# POWER_MC33063.net
KiCad netlist of a schematic drawn in Altium Designer
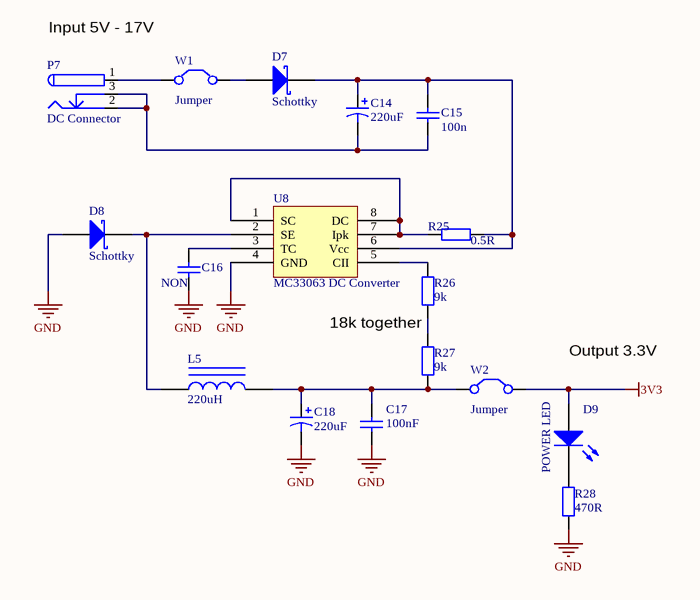
[diagram p0: POWER_MC33063.SchDoc]

(export (version "E")
  (design (tool "Eeschema 10.0.6"))
  (components
    (comp (ref "C14")
      (value "220uF")
      (footprint "SMD CAPACITOR 220uF")
      (description "Capacitor")
      (fields (field (name "PUBLISHER") "Altium Limited"))
      (libsource (lib "Miscellaneous Devices") (part "Cap Pol1"))
    )
    (comp (ref "C15")
      (value "100n")
      (footprint "1608[0603]")
      (description "Capacitor")
      (fields (field (name "PUBLISHER") "Altium Limited"))
      (libsource (lib "Miscellaneous Devices") (part "Cap"))
    )
    (comp (ref "C16")
      (value "NON")
      (footprint "1608[0603]")
      (description "Capacitor")
      (fields (field (name "PUBLISHER") "Altium Limited"))
      (libsource (lib "Miscellaneous Devices") (part "Cap"))
    )
    (comp (ref "C17")
      (value "100nF")
      (footprint "1608[0603]")
      (description "Capacitor")
      (fields (field (name "PUBLISHER") "Altium Limited"))
      (libsource (lib "Miscellaneous Devices") (part "Cap"))
    )
    (comp (ref "C18")
      (value "220uF")
      (footprint "SMD CAPACITOR 220uF")
      (description "Polarized Capacitor (Radial)")
      (fields (field (name "PUBLISHER") "Altium Limited"))
      (libsource (lib "Miscellaneous Devices") (part "Cap Pol1"))
    )
    (comp (ref "D7")
      (value "Schottky")
      (footprint "SMB")
      (description "Schottky Diode")
      (fields (field (name "PUBLISHER") "Altium Limited"))
      (libsource (lib "Miscellaneous Devices") (part "D Schottky"))
    )
    (comp (ref "D8")
      (value "Schottky")
      (footprint "SMB")
      (description "Schottky Diode")
      (fields (field (name "PUBLISHER") "Altium Limited"))
      (libsource (lib "Miscellaneous Devices") (part "D Schottky"))
    )
    (comp (ref "D9")
      (value "POWER LED")
      (footprint "LED-1")
      (description "Typical INFRARED GaAs LED")
      (fields (field (name "PUBLISHER") "Altium Limited"))
      (libsource (lib "Miscellaneous Devices") (part "LED0"))
    )
    (comp (ref "L5")
      (value "220uH")
      (footprint "Inductor")
      (description "Magnetic-Core Inductor")
      (fields (field (name "PUBLISHER") "Altium Limited"))
      (libsource (lib "Miscellaneous Devices") (part "Inductor Iron"))
    )
    (comp (ref "P7")
      (value "DC Connector")
      (footprint "DC Connector")
      (description "DC Power Connector")
      (libsource (lib "LukaLIBRARY") (part "DC Connector"))
    )
    (comp (ref "R25")
      (value "0.5R")
      (footprint "1608[0603]")
      (description "Resistor")
      (fields (field (name "PUBLISHER") "Altium Limited"))
      (libsource (lib "") (part "Res2_1"))
    )
    (comp (ref "R26")
      (value "9k")
      (footprint "1608[0603]")
      (description "Resistor")
      (fields (field (name "PUBLISHER") "Altium Limited"))
      (libsource (lib "Miscellaneous Devices") (part "Res2"))
    )
    (comp (ref "R27")
      (value "9k")
      (footprint "1608[0603]")
      (description "Resistor")
      (fields (field (name "PUBLISHER") "Altium Limited"))
      (libsource (lib "Miscellaneous Devices") (part "Res2"))
    )
    (comp (ref "R28")
      (value "470R")
      (footprint "1608[0603]")
      (description "Resistor")
      (fields (field (name "PUBLISHER") "Altium Limited"))
      (libsource (lib "Miscellaneous Devices") (part "Res2"))
    )
    (comp (ref "U8")
      (value "MC33063 DC Converter")
      (footprint "SO8_N")
      (libsource (lib "LukaLIBRARY") (part "MC33063 - MC34063 DC DC"))
    )
    (comp (ref "W1")
      (value "Jumper")
      (footprint "HDR1X2")
      (description "Jumper Wire")
      (fields (field (name "PUBLISHER") "Altium Limited"))
      (libsource (lib "Miscellaneous Devices") (part "Jumper"))
    )
    (comp (ref "W2")
      (value "Jumper")
      (footprint "C0805")
      (description "Jumper Wire")
      (fields (field (name "PUBLISHER") "Altium Limited"))
      (libsource (lib "Miscellaneous Devices") (part "Jumper"))
    )
  )
  (nets
    (net (code "1") (name "3V3") (class "Default")
      (node (ref "D9") (pin "1") (pinfunction "A_1") (pintype "passive"))
      (node (ref "W2") (pin "2") (pinfunction "C2_2") (pintype "passive"))
    )
    (net (code "2") (name "GND") (class "Default")
      (node (ref "C16") (pin "1") (pinfunction "1_1") (pintype "passive"))
      (node (ref "C17") (pin "1") (pinfunction "1_1") (pintype "passive"))
      (node (ref "C18") (pin "2") (pinfunction "2_2") (pintype "passive"))
      (node (ref "D8") (pin "1") (pinfunction "A_1") (pintype "passive"))
      (node (ref "R28") (pin "1") (pinfunction "1_1") (pintype "passive"))
      (node (ref "U8") (pin "4") (pinfunction "GND_4") (pintype "passive"))
    )
    (net (code "3") (name "Net-(C14-Pad2)") (class "Default")
      (node (ref "C14") (pin "2") (pinfunction "2_2") (pintype "passive"))
      (node (ref "C15") (pin "2") (pinfunction "2_2") (pintype "passive"))
      (node (ref "P7") (pin "2") (pinfunction "2_2") (pintype "power_in"))
      (node (ref "P7") (pin "3") (pinfunction "3_3") (pintype "power_in"))
    )
    (net (code "4") (name "Net-(D7-A)") (class "Default")
      (node (ref "D7") (pin "1") (pinfunction "A_1") (pintype "passive"))
      (node (ref "W1") (pin "2") (pinfunction "C2_2") (pintype "passive"))
    )
    (net (code "5") (name "Net-(D7-K)") (class "Default")
      (node (ref "C14") (pin "1") (pinfunction "1_1") (pintype "passive"))
      (node (ref "C15") (pin "1") (pinfunction "1_1") (pintype "passive"))
      (node (ref "D7") (pin "2") (pinfunction "K_2") (pintype "passive"))
      (node (ref "R25") (pin "1") (pinfunction "1_1") (pintype "passive"))
      (node (ref "U8") (pin "6") (pinfunction "Vcc_6") (pintype "passive"))
    )
    (net (code "6") (name "Net-(D8-K)") (class "Default")
      (node (ref "D8") (pin "2") (pinfunction "K_2") (pintype "passive"))
      (node (ref "L5") (pin "1") (pinfunction "1_1") (pintype "passive"))
      (node (ref "U8") (pin "2") (pinfunction "SE_2") (pintype "passive"))
    )
    (net (code "7") (name "Net-(D9-K)") (class "Default")
      (node (ref "D9") (pin "2") (pinfunction "K_2") (pintype "passive"))
      (node (ref "R28") (pin "2") (pinfunction "2_2") (pintype "passive"))
    )
    (net (code "8") (name "Net-(R26-Pad1)") (class "Default")
      (node (ref "R26") (pin "1") (pinfunction "1_1") (pintype "passive"))
      (node (ref "R27") (pin "2") (pinfunction "2_2") (pintype "passive"))
    )
    (net (code "9") (name "Net-(U8-CII)") (class "Default")
      (node (ref "R26") (pin "2") (pinfunction "2_2") (pintype "passive"))
      (node (ref "U8") (pin "5") (pinfunction "CII_5") (pintype "passive"))
    )
    (net (code "10") (name "Net-(U8-DC)") (class "Default")
      (node (ref "R25") (pin "2") (pinfunction "2_2") (pintype "passive"))
      (node (ref "U8") (pin "1") (pinfunction "SC_1") (pintype "passive"))
      (node (ref "U8") (pin "7") (pinfunction "Ipk_7") (pintype "passive"))
      (node (ref "U8") (pin "8") (pinfunction "DC_8") (pintype "passive"))
    )
    (net (code "11") (name "Net-(U8-TC)") (class "Default")
      (node (ref "C16") (pin "2") (pinfunction "2_2") (pintype "passive"))
      (node (ref "U8") (pin "3") (pinfunction "TC_3") (pintype "passive"))
    )
    (net (code "12") (name "Net-(W1-C1)") (class "Default")
      (node (ref "P7") (pin "1") (pinfunction "1_1") (pintype "power_in"))
      (node (ref "W1") (pin "1") (pinfunction "C1_1") (pintype "passive"))
    )
    (net (code "13") (name "Net-(W2-C1)") (class "Default")
      (node (ref "C17") (pin "2") (pinfunction "2_2") (pintype "passive"))
      (node (ref "C18") (pin "1") (pinfunction "1_1") (pintype "passive"))
      (node (ref "L5") (pin "2") (pinfunction "2_2") (pintype "passive"))
      (node (ref "R27") (pin "1") (pinfunction "1_1") (pintype "passive"))
      (node (ref "W2") (pin "1") (pinfunction "C1_1") (pintype "passive"))
    )
  )
)
